# USB_nRF24L01_gateway.net
KiCad netlist of a schematic drawn in Altium Designer
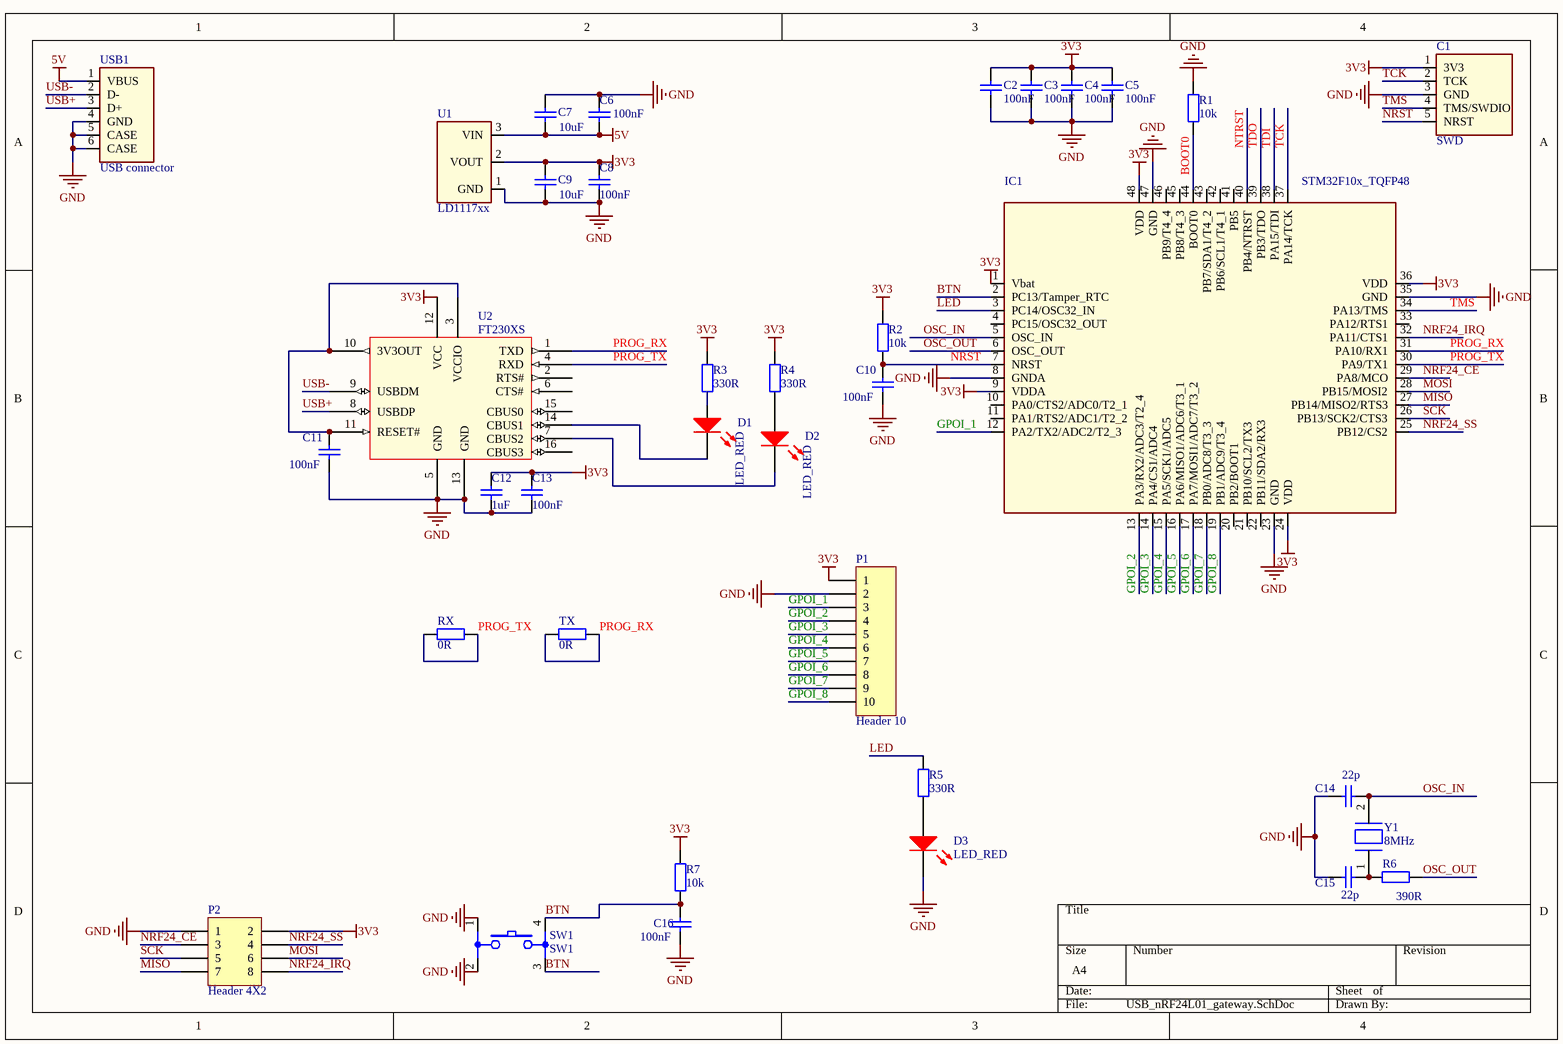
[diagram p0: USB_nRF24L01_gateway.SchDoc]

(export (version "E")
  (design (tool "Eeschema 10.0.6"))
  (components
    (comp (ref "C1")
      (value "SWD")
      (footprint "SWD")
      (description "ARM SWD connector")
      (libsource (lib "Connector") (part "SWD"))
    )
    (comp (ref "C2")
      (value "100nF")
      (footprint "FP_0603_CAP_080")
      (description "Capacitor")
      (libsource (lib "Miscellaneous Devices") (part "Cap"))
    )
    (comp (ref "C3")
      (value "100nF")
      (footprint "FP_0603_CAP_080")
      (description "Capacitor")
      (libsource (lib "Miscellaneous Devices") (part "Cap"))
    )
    (comp (ref "C4")
      (value "100nF")
      (footprint "FP_0603_CAP_080")
      (description "Capacitor")
      (libsource (lib "Miscellaneous Devices") (part "Cap"))
    )
    (comp (ref "C5")
      (value "100nF")
      (footprint "FP_0603_CAP_080")
      (description "Capacitor")
      (libsource (lib "Miscellaneous Devices") (part "Cap"))
    )
    (comp (ref "C6")
      (value "100nF")
      (footprint "FP_0603_CAP_080")
      (description "Capacitor")
      (fields (field (name "PUBLISHER") "Altium Limited"))
      (libsource (lib "Miscellaneous Devices") (part "Cap"))
    )
    (comp (ref "C7")
      (value "10uF")
      (footprint "FP_1206_CAP_085")
      (description "Capacitor")
      (fields (field (name "PUBLISHER") "Altium Limited"))
      (libsource (lib "Miscellaneous Devices") (part "Cap"))
    )
    (comp (ref "C8")
      (value "100nF")
      (footprint "FP_0603_CAP_080")
      (description "Capacitor")
      (fields (field (name "PUBLISHER") "Altium Limited"))
      (libsource (lib "Miscellaneous Devices") (part "Cap"))
    )
    (comp (ref "C9")
      (value "10uF")
      (footprint "FP_1206_CAP_085")
      (description "Capacitor")
      (fields (field (name "PUBLISHER") "Altium Limited"))
      (libsource (lib "Miscellaneous Devices") (part "Cap"))
    )
    (comp (ref "C10")
      (value "100nF")
      (footprint "FP_0603_CAP_080")
      (description "Capacitor")
      (libsource (lib "Miscellaneous Devices") (part "Cap"))
    )
    (comp (ref "C11")
      (value "100nF")
      (footprint "FP_0603_CAP_080")
      (description "Capacitor")
      (libsource (lib "Miscellaneous Devices") (part "Cap"))
    )
    (comp (ref "C12")
      (value "1uF")
      (footprint "FP_0603_CAP_080")
      (description "Capacitor")
      (fields (field (name "PUBLISHER") "Altium Limited"))
      (libsource (lib "Miscellaneous Devices") (part "Cap"))
    )
    (comp (ref "C13")
      (value "100nF")
      (footprint "FP_0603_CAP_080")
      (description "Capacitor")
      (fields (field (name "PUBLISHER") "Altium Limited"))
      (libsource (lib "Miscellaneous Devices") (part "Cap"))
    )
    (comp (ref "C14")
      (value "22p")
      (footprint "FP_0603_CAP_080")
      (description "Capacitor")
      (libsource (lib "Miscellaneous Devices") (part "Cap"))
    )
    (comp (ref "C15")
      (value "22p")
      (footprint "FP_0603_CAP_080")
      (description "Capacitor")
      (libsource (lib "Miscellaneous Devices") (part "Cap"))
    )
    (comp (ref "C16")
      (value "100nF")
      (footprint "FP_0603_CAP_080")
      (description "Capacitor")
      (libsource (lib "Miscellaneous Devices") (part "Cap"))
    )
    (comp (ref "D1")
      (value "LED_RED")
      (footprint "FP_0805_LED_RED")
      (description "Typical LED")
      (libsource (lib "Led_optical") (part "LED_R"))
    )
    (comp (ref "D2")
      (value "LED_RED")
      (footprint "FP_0805_LED_RED")
      (description "Typical LED")
      (libsource (lib "Led_optical") (part "LED_R"))
    )
    (comp (ref "D3")
      (value "LED_RED")
      (footprint "FP_0805_LED_RED")
      (description "Typical LED")
      (libsource (lib "Led_optical") (part "LED_R"))
    )
    (comp (ref "IC1")
      (value "STM32F10x_TQFP48")
      (footprint "LQFP48_N")
      (libsource (lib "uC") (part "STM32F10x_TQFP48"))
    )
    (comp (ref "P1")
      (value "Header 10")
      (footprint "HDR1X10")
      (description "Header, 10-Pin")
      (fields (field (name "PUBLISHER") "Altium Limited"))
      (libsource (lib "Miscellaneous Connectors") (part "Header 10"))
    )
    (comp (ref "P2")
      (value "Header 4X2")
      (footprint "FP_CONN8_SZK_ALLO")
      (description "Header, 4-Pin, Dual row")
      (fields (field (name "PUBLISHER") "Altium Limited"))
      (libsource (lib "Miscellaneous Connectors") (part "Header 4X2"))
    )
    (comp (ref "R1")
      (value "10k")
      (footprint "FP_0603_RES")
      (description "Resistor")
      (libsource (lib "Miscellaneous Devices") (part "Res3"))
    )
    (comp (ref "R2")
      (value "10k")
      (footprint "FP_0603_RES")
      (description "Resistor")
      (libsource (lib "Miscellaneous Devices") (part "Res3"))
    )
    (comp (ref "R3")
      (value "330R")
      (footprint "FP_0603_RES")
      (description "Resistor")
      (fields (field (name "PUBLISHER") "Altium Limited"))
      (libsource (lib "Miscellaneous Devices") (part "Res3"))
    )
    (comp (ref "R4")
      (value "330R")
      (footprint "FP_0603_RES")
      (description "Resistor")
      (fields (field (name "PUBLISHER") "Altium Limited"))
      (libsource (lib "Miscellaneous Devices") (part "Res3"))
    )
    (comp (ref "R5")
      (value "330R")
      (footprint "FP_0603_RES")
      (description "Resistor")
      (fields (field (name "PUBLISHER") "Altium Limited"))
      (libsource (lib "Miscellaneous Devices") (part "Res3"))
    )
    (comp (ref "R6")
      (value "390R")
      (footprint "FP_0603_RES")
      (description "Resistor")
      (libsource (lib "") (part "Res3_2"))
    )
    (comp (ref "R7")
      (value "10k")
      (footprint "FP_0603_RES")
      (description "Resistor")
      (libsource (lib "Miscellaneous Devices") (part "Res3"))
    )
    (comp (ref "RX")
      (value "0R")
      (footprint "FP_0603_RES")
      (description "Resistor")
      (fields (field (name "PUBLISHER") "Altium Limited"))
      (libsource (lib "") (part "Res3_1"))
    )
    (comp (ref "SW1") (value "SW1") (footprint "FP_TACTBTN") (libsource (lib "Switch") (part "SW1")))
    (comp (ref "TX")
      (value "0R")
      (footprint "FP_0603_RES")
      (description "Resistor")
      (fields (field (name "PUBLISHER") "Altium Limited"))
      (libsource (lib "") (part "Res3_1"))
    )
    (comp (ref "U1")
      (value "LD1117xx")
      (footprint "SUPPLY_SOT223")
      (description "LD1117xx 3,3V lin reg")
      (libsource (lib "Supply") (part "LD1117xx"))
    )
    (comp (ref "U2")
      (value "FT230XS")
      (footprint "Digital_TSSOP16")
      (description "USB-SERIAL")
      (libsource (lib "Digital") (part "FT230XS"))
    )
    (comp (ref "USB1")
      (value "USB connector")
      (footprint "USB_A_th")
      (description "USB B conn TH")
      (libsource (lib "Connector") (part "USB_B_TH"))
    )
    (comp (ref "Y1")
      (value "8MHz")
      (footprint "FP_CRYSTAL_HC49_TH")
      (description "Standard HC49 quartz")
      (fields (field (name "Comment") "8MHz Quartz HC49"))
      (libsource (lib "Fufi_altium_lib") (part "XTAL HC49"))
    )
  )
  (nets
    (net (code "1") (name "/BOOT0") (class "Default")
      (node (ref "IC1") (pin "44") (pinfunction "BOOT0_44") (pintype "passive"))
      (node (ref "R1") (pin "2") (pinfunction "2_2") (pintype "passive"))
    )
    (net (code "2") (name "/BTN") (class "Default")
      (node (ref "C16") (pin "1") (pinfunction "1_1") (pintype "passive"))
      (node (ref "IC1") (pin "2") (pinfunction "PC13/Tamper_RTC_2") (pintype "passive"))
      (node (ref "R7") (pin "2") (pinfunction "2_2") (pintype "passive"))
      (node (ref "SW1") (pin "3") (pinfunction "3_3") (pintype "passive"))
      (node (ref "SW1") (pin "4") (pinfunction "4_4") (pintype "passive"))
    )
    (net (code "3") (name "/GPOI_1") (class "Default")
      (node (ref "IC1") (pin "12") (pinfunction "PA2/TX2/ADC2/T2_3_12") (pintype "passive"))
      (node (ref "P1") (pin "3") (pinfunction "3_3") (pintype "passive"))
    )
    (net (code "4") (name "/GPOI_2") (class "Default")
      (node (ref "IC1") (pin "13") (pinfunction "PA3/RX2/ADC3/T2_4_13") (pintype "passive"))
      (node (ref "P1") (pin "4") (pinfunction "4_4") (pintype "passive"))
    )
    (net (code "5") (name "/GPOI_3") (class "Default")
      (node (ref "IC1") (pin "14") (pinfunction "PA4/CS1/ADC4_14") (pintype "passive"))
      (node (ref "P1") (pin "5") (pinfunction "5_5") (pintype "passive"))
    )
    (net (code "6") (name "/GPOI_4") (class "Default")
      (node (ref "IC1") (pin "15") (pinfunction "PA5/SCK1/ADC5_15") (pintype "passive"))
      (node (ref "P1") (pin "6") (pinfunction "6_6") (pintype "passive"))
    )
    (net (code "7") (name "/GPOI_5") (class "Default")
      (node (ref "IC1") (pin "16") (pinfunction "PA6/MISO1/ADC6/T3_1_16") (pintype "passive"))
      (node (ref "P1") (pin "7") (pinfunction "7_7") (pintype "passive"))
    )
    (net (code "8") (name "/GPOI_6") (class "Default")
      (node (ref "IC1") (pin "17") (pinfunction "PA7/MOSI1/ADC7/T3_2_17") (pintype "passive"))
      (node (ref "P1") (pin "8") (pinfunction "8_8") (pintype "passive"))
    )
    (net (code "9") (name "/GPOI_7") (class "Default")
      (node (ref "IC1") (pin "18") (pinfunction "PB0/ADC8/T3_3_18") (pintype "passive"))
      (node (ref "P1") (pin "9") (pinfunction "9_9") (pintype "passive"))
    )
    (net (code "10") (name "/GPOI_8") (class "Default")
      (node (ref "IC1") (pin "19") (pinfunction "PB1/ADC9/T3_4_19") (pintype "passive"))
      (node (ref "P1") (pin "10") (pinfunction "10_10") (pintype "passive"))
    )
    (net (code "11") (name "/LED") (class "Default")
      (node (ref "IC1") (pin "3") (pinfunction "PC14/OSC32_IN_3") (pintype "passive"))
      (node (ref "R5") (pin "1") (pinfunction "1_1") (pintype "passive"))
    )
    (net (code "12") (name "/MISO") (class "Default")
      (node (ref "IC1") (pin "27") (pinfunction "PB14/MISO2/RTS3_27") (pintype "passive"))
      (node (ref "P2") (pin "7") (pinfunction "7_7") (pintype "passive"))
    )
    (net (code "13") (name "/MOSI") (class "Default")
      (node (ref "IC1") (pin "28") (pinfunction "PB15/MOSI2_28") (pintype "passive"))
      (node (ref "P2") (pin "6") (pinfunction "6_6") (pintype "passive"))
    )
    (net (code "14") (name "/NRF24_CE") (class "Default")
      (node (ref "IC1") (pin "29") (pinfunction "PA8/MCO_29") (pintype "passive"))
      (node (ref "P2") (pin "3") (pinfunction "3_3") (pintype "passive"))
    )
    (net (code "15") (name "/NRF24_IRQ") (class "Default")
      (node (ref "IC1") (pin "32") (pinfunction "PA11/CTS1_32") (pintype "passive"))
      (node (ref "P2") (pin "8") (pinfunction "8_8") (pintype "passive"))
    )
    (net (code "16") (name "/NRF24_SS") (class "Default")
      (node (ref "IC1") (pin "25") (pinfunction "PB12/CS2_25") (pintype "passive"))
      (node (ref "P2") (pin "4") (pinfunction "4_4") (pintype "passive"))
    )
    (net (code "17") (name "/NRST") (class "Default")
      (node (ref "C1") (pin "5") (pinfunction "NRST_5") (pintype "passive"))
      (node (ref "C10") (pin "1") (pinfunction "1_1") (pintype "passive"))
      (node (ref "IC1") (pin "7") (pinfunction "NRST_7") (pintype "passive"))
      (node (ref "R2") (pin "2") (pinfunction "2_2") (pintype "passive"))
    )
    (net (code "18") (name "/NTRST") (class "Default")
      (node (ref "IC1") (pin "40") (pinfunction "PB4/NTRST_40") (pintype "passive"))
    )
    (net (code "19") (name "/OSC_IN") (class "Default")
      (node (ref "C14") (pin "2") (pinfunction "2_2") (pintype "passive"))
      (node (ref "IC1") (pin "5") (pinfunction "OSC_IN_5") (pintype "passive"))
      (node (ref "Y1") (pin "2") (pinfunction "2_2") (pintype "passive"))
    )
    (net (code "20") (name "/OSC_OUT") (class "Default")
      (node (ref "IC1") (pin "6") (pinfunction "OSC_OUT_6") (pintype "passive"))
      (node (ref "R6") (pin "1") (pinfunction "1_1") (pintype "passive"))
    )
    (net (code "21") (name "/PROG_RX") (class "Default")
      (node (ref "IC1") (pin "31") (pinfunction "PA10/RX1_31") (pintype "passive"))
      (node (ref "TX") (pin "1") (pinfunction "1_1") (pintype "passive"))
      (node (ref "TX") (pin "2") (pinfunction "2_2") (pintype "passive"))
      (node (ref "U2") (pin "1") (pinfunction "TXD_1") (pintype "output"))
    )
    (net (code "22") (name "/PROG_TX") (class "Default")
      (node (ref "IC1") (pin "30") (pinfunction "PA9/TX1_30") (pintype "passive"))
      (node (ref "RX") (pin "1") (pinfunction "1_1") (pintype "passive"))
      (node (ref "RX") (pin "2") (pinfunction "2_2") (pintype "passive"))
      (node (ref "U2") (pin "4") (pinfunction "RXD_4") (pintype "input"))
    )
    (net (code "23") (name "/SCK") (class "Default")
      (node (ref "IC1") (pin "26") (pinfunction "PB13/SCK2/CTS3_26") (pintype "passive"))
      (node (ref "P2") (pin "5") (pinfunction "5_5") (pintype "passive"))
    )
    (net (code "24") (name "/TCK") (class "Default")
      (node (ref "C1") (pin "2") (pinfunction "TCK_2") (pintype "passive"))
      (node (ref "IC1") (pin "37") (pinfunction "PA14/TCK_37") (pintype "passive"))
    )
    (net (code "25") (name "/TDI") (class "Default")
      (node (ref "IC1") (pin "38") (pinfunction "PA15/TDI_38") (pintype "passive"))
    )
    (net (code "26") (name "/TDO") (class "Default")
      (node (ref "IC1") (pin "39") (pinfunction "PB3/TDO_39") (pintype "passive"))
    )
    (net (code "27") (name "/TMS") (class "Default")
      (node (ref "C1") (pin "4") (pinfunction "TMS/SWDIO_4") (pintype "passive"))
      (node (ref "IC1") (pin "34") (pinfunction "PA13/TMS_34") (pintype "passive"))
    )
    (net (code "28") (name "/USB+") (class "Default")
      (node (ref "U2") (pin "8") (pinfunction "USBDP_8") (pintype "bidirectional"))
      (node (ref "USB1") (pin "3") (pinfunction "D+_3") (pintype "passive"))
    )
    (net (code "29") (name "/USB-") (class "Default")
      (node (ref "U2") (pin "9") (pinfunction "USBDM_9") (pintype "bidirectional"))
      (node (ref "USB1") (pin "2") (pinfunction "D-_2") (pintype "passive"))
    )
    (net (code "30") (name "3V3") (class "Default")
      (node (ref "C1") (pin "1") (pinfunction "3V3_1") (pintype "passive"))
      (node (ref "C12") (pin "1") (pinfunction "1_1") (pintype "passive"))
      (node (ref "C13") (pin "1") (pinfunction "1_1") (pintype "passive"))
      (node (ref "C2") (pin "2") (pinfunction "2_2") (pintype "passive"))
      (node (ref "C3") (pin "2") (pinfunction "2_2") (pintype "passive"))
      (node (ref "C4") (pin "2") (pinfunction "2_2") (pintype "passive"))
      (node (ref "C5") (pin "2") (pinfunction "2_2") (pintype "passive"))
      (node (ref "C8") (pin "1") (pinfunction "1_1") (pintype "passive"))
      (node (ref "C9") (pin "2") (pinfunction "2_2") (pintype "passive"))
      (node (ref "IC1") (pin "1") (pinfunction "Vbat_1") (pintype "passive"))
      (node (ref "IC1") (pin "24") (pinfunction "VDD_24") (pintype "passive"))
      (node (ref "IC1") (pin "36") (pinfunction "VDD_36") (pintype "passive"))
      (node (ref "IC1") (pin "48") (pinfunction "VDD_48") (pintype "passive"))
      (node (ref "IC1") (pin "9") (pinfunction "VDDA_9") (pintype "passive"))
      (node (ref "P1") (pin "1") (pinfunction "1_1") (pintype "passive"))
      (node (ref "P2") (pin "2") (pinfunction "2_2") (pintype "passive"))
      (node (ref "R2") (pin "1") (pinfunction "1_1") (pintype "passive"))
      (node (ref "R3") (pin "1") (pinfunction "1_1") (pintype "passive"))
      (node (ref "R4") (pin "1") (pinfunction "1_1") (pintype "passive"))
      (node (ref "R7") (pin "1") (pinfunction "1_1") (pintype "passive"))
      (node (ref "U1") (pin "2") (pinfunction "VOUT_2") (pintype "passive"))
      (node (ref "U2") (pin "12") (pinfunction "VCC_12") (pintype "power_in"))
    )
    (net (code "31") (name "5V") (class "Default")
      (node (ref "C6") (pin "2") (pinfunction "2_2") (pintype "passive"))
      (node (ref "C7") (pin "1") (pinfunction "1_1") (pintype "passive"))
      (node (ref "U1") (pin "3") (pinfunction "VIN_3") (pintype "passive"))
      (node (ref "USB1") (pin "1") (pinfunction "VBUS_1") (pintype "passive"))
    )
    (net (code "32") (name "GND") (class "Default")
      (node (ref "C1") (pin "3") (pinfunction "GND_3") (pintype "passive"))
      (node (ref "C10") (pin "2") (pinfunction "2_2") (pintype "passive"))
      (node (ref "C11") (pin "2") (pinfunction "2_2") (pintype "passive"))
      (node (ref "C12") (pin "2") (pinfunction "2_2") (pintype "passive"))
      (node (ref "C13") (pin "2") (pinfunction "2_2") (pintype "passive"))
      (node (ref "C14") (pin "1") (pinfunction "1_1") (pintype "passive"))
      (node (ref "C15") (pin "1") (pinfunction "1_1") (pintype "passive"))
      (node (ref "C16") (pin "2") (pinfunction "2_2") (pintype "passive"))
      (node (ref "C2") (pin "1") (pinfunction "1_1") (pintype "passive"))
      (node (ref "C3") (pin "1") (pinfunction "1_1") (pintype "passive"))
      (node (ref "C4") (pin "1") (pinfunction "1_1") (pintype "passive"))
      (node (ref "C5") (pin "1") (pinfunction "1_1") (pintype "passive"))
      (node (ref "C6") (pin "1") (pinfunction "1_1") (pintype "passive"))
      (node (ref "C7") (pin "2") (pinfunction "2_2") (pintype "passive"))
      (node (ref "C8") (pin "2") (pinfunction "2_2") (pintype "passive"))
      (node (ref "C9") (pin "1") (pinfunction "1_1") (pintype "passive"))
      (node (ref "D3") (pin "K") (pinfunction "K_K") (pintype "passive"))
      (node (ref "IC1") (pin "23") (pinfunction "GND_23") (pintype "passive"))
      (node (ref "IC1") (pin "35") (pinfunction "GND_35") (pintype "passive"))
      (node (ref "IC1") (pin "47") (pinfunction "GND_47") (pintype "passive"))
      (node (ref "IC1") (pin "8") (pinfunction "GNDA_8") (pintype "passive"))
      (node (ref "P1") (pin "2") (pinfunction "2_2") (pintype "passive"))
      (node (ref "P2") (pin "1") (pinfunction "1_1") (pintype "passive"))
      (node (ref "R1") (pin "1") (pinfunction "1_1") (pintype "passive"))
      (node (ref "SW1") (pin "1") (pinfunction "1_1") (pintype "passive"))
      (node (ref "SW1") (pin "2") (pinfunction "2_2") (pintype "passive"))
      (node (ref "U1") (pin "1") (pinfunction "GND_1") (pintype "passive"))
      (node (ref "U2") (pin "13") (pinfunction "GND_13") (pintype "power_in"))
      (node (ref "U2") (pin "5") (pinfunction "GND_5") (pintype "power_in"))
      (node (ref "USB1") (pin "4") (pinfunction "GND_4") (pintype "passive"))
      (node (ref "USB1") (pin "5") (pinfunction "CASE_5") (pintype "passive"))
      (node (ref "USB1") (pin "6") (pinfunction "CASE_6") (pintype "passive"))
    )
    (net (code "33") (name "Net-(C15-Pad2)") (class "Default")
      (node (ref "C15") (pin "2") (pinfunction "2_2") (pintype "passive"))
      (node (ref "R6") (pin "2") (pinfunction "2_2") (pintype "passive"))
      (node (ref "Y1") (pin "1") (pinfunction "1_1") (pintype "passive"))
    )
    (net (code "34") (name "Net-(D1-PadA)") (class "Default")
      (node (ref "D1") (pin "A") (pinfunction "A_A") (pintype "passive"))
      (node (ref "R3") (pin "2") (pinfunction "2_2") (pintype "passive"))
    )
    (net (code "35") (name "Net-(D2-PadA)") (class "Default")
      (node (ref "D2") (pin "A") (pinfunction "A_A") (pintype "passive"))
      (node (ref "R4") (pin "2") (pinfunction "2_2") (pintype "passive"))
    )
    (net (code "36") (name "Net-(D3-PadA)") (class "Default")
      (node (ref "D3") (pin "A") (pinfunction "A_A") (pintype "passive"))
      (node (ref "R5") (pin "2") (pinfunction "2_2") (pintype "passive"))
    )
    (net (code "37") (name "Net-(U2-3V3OUT)") (class "Default")
      (node (ref "C11") (pin "1") (pinfunction "1_1") (pintype "passive"))
      (node (ref "U2") (pin "10") (pinfunction "3V3OUT_10") (pintype "output"))
      (node (ref "U2") (pin "11") (pinfunction "RESET#_11") (pintype "input"))
      (node (ref "U2") (pin "3") (pinfunction "VCCIO_3") (pintype "power_in"))
    )
    (net (code "38") (name "Net-(U2-CBUS1)") (class "Default")
      (node (ref "D1") (pin "K") (pinfunction "K_K") (pintype "passive"))
      (node (ref "U2") (pin "14") (pinfunction "CBUS1_14") (pintype "bidirectional"))
    )
    (net (code "39") (name "Net-(U2-CBUS2)") (class "Default")
      (node (ref "D2") (pin "K") (pinfunction "K_K") (pintype "passive"))
      (node (ref "U2") (pin "7") (pinfunction "CBUS2_7") (pintype "bidirectional"))
    )
    (net (code "40") (name "unconnected-(IC1-PA0{slash}CTS2{slash}ADC0{slash}T2_1-Pad10)") (class "Default")
      (node (ref "IC1") (pin "10") (pinfunction "PA0/CTS2/ADC0/T2_1_10") (pintype "passive"))
    )
    (net (code "41") (name "unconnected-(IC1-PA1{slash}RTS2{slash}ADC1{slash}T2_2-Pad11)") (class "Default")
      (node (ref "IC1") (pin "11") (pinfunction "PA1/RTS2/ADC1/T2_2_11") (pintype "passive"))
    )
    (net (code "42") (name "unconnected-(IC1-PA12{slash}RTS1-Pad33)") (class "Default")
      (node (ref "IC1") (pin "33") (pinfunction "PA12/RTS1_33") (pintype "passive"))
    )
    (net (code "43") (name "unconnected-(IC1-PB2{slash}BOOT1-Pad20)") (class "Default")
      (node (ref "IC1") (pin "20") (pinfunction "PB2/BOOT1_20") (pintype "passive"))
    )
    (net (code "44") (name "unconnected-(IC1-PB5-Pad41)") (class "Default")
      (node (ref "IC1") (pin "41") (pinfunction "PB5_41") (pintype "passive"))
    )
    (net (code "45") (name "unconnected-(IC1-PB6{slash}SCL1{slash}T4_1-Pad42)") (class "Default")
      (node (ref "IC1") (pin "42") (pinfunction "PB6/SCL1/T4_1_42") (pintype "passive"))
    )
    (net (code "46") (name "unconnected-(IC1-PB7{slash}SDA1{slash}T4_2-Pad43)") (class "Default")
      (node (ref "IC1") (pin "43") (pinfunction "PB7/SDA1/T4_2_43") (pintype "passive"))
    )
    (net (code "47") (name "unconnected-(IC1-PB8{slash}T4_3-Pad45)") (class "Default")
      (node (ref "IC1") (pin "45") (pinfunction "PB8/T4_3_45") (pintype "passive"))
    )
    (net (code "48") (name "unconnected-(IC1-PB9{slash}T4_4-Pad46)") (class "Default")
      (node (ref "IC1") (pin "46") (pinfunction "PB9/T4_4_46") (pintype "passive"))
    )
    (net (code "49") (name "unconnected-(IC1-PB10{slash}SCL2{slash}TX3-Pad21)") (class "Default")
      (node (ref "IC1") (pin "21") (pinfunction "PB10/SCL2/TX3_21") (pintype "passive"))
    )
    (net (code "50") (name "unconnected-(IC1-PB11{slash}SDA2{slash}RX3-Pad22)") (class "Default")
      (node (ref "IC1") (pin "22") (pinfunction "PB11/SDA2/RX3_22") (pintype "passive"))
    )
    (net (code "51") (name "unconnected-(IC1-PC15{slash}OSC32_OUT-Pad4)") (class "Default")
      (node (ref "IC1") (pin "4") (pinfunction "PC15/OSC32_OUT_4") (pintype "passive"))
    )
    (net (code "52") (name "unconnected-(U2-CBUS0-Pad15)") (class "Default")
      (node (ref "U2") (pin "15") (pinfunction "CBUS0_15") (pintype "bidirectional"))
    )
    (net (code "53") (name "unconnected-(U2-CBUS3-Pad16)") (class "Default")
      (node (ref "U2") (pin "16") (pinfunction "CBUS3_16") (pintype "bidirectional"))
    )
    (net (code "54") (name "unconnected-(U2-CTS#-Pad6)") (class "Default")
      (node (ref "U2") (pin "6") (pinfunction "CTS#_6") (pintype "input"))
    )
    (net (code "55") (name "unconnected-(U2-RTS#-Pad2)") (class "Default")
      (node (ref "U2") (pin "2") (pinfunction "RTS#_2") (pintype "output"))
    )
  )
)
